# eurorack-passive-diodefuzz-5switches.net
KiCad netlist of a schematic drawn in EAGLE
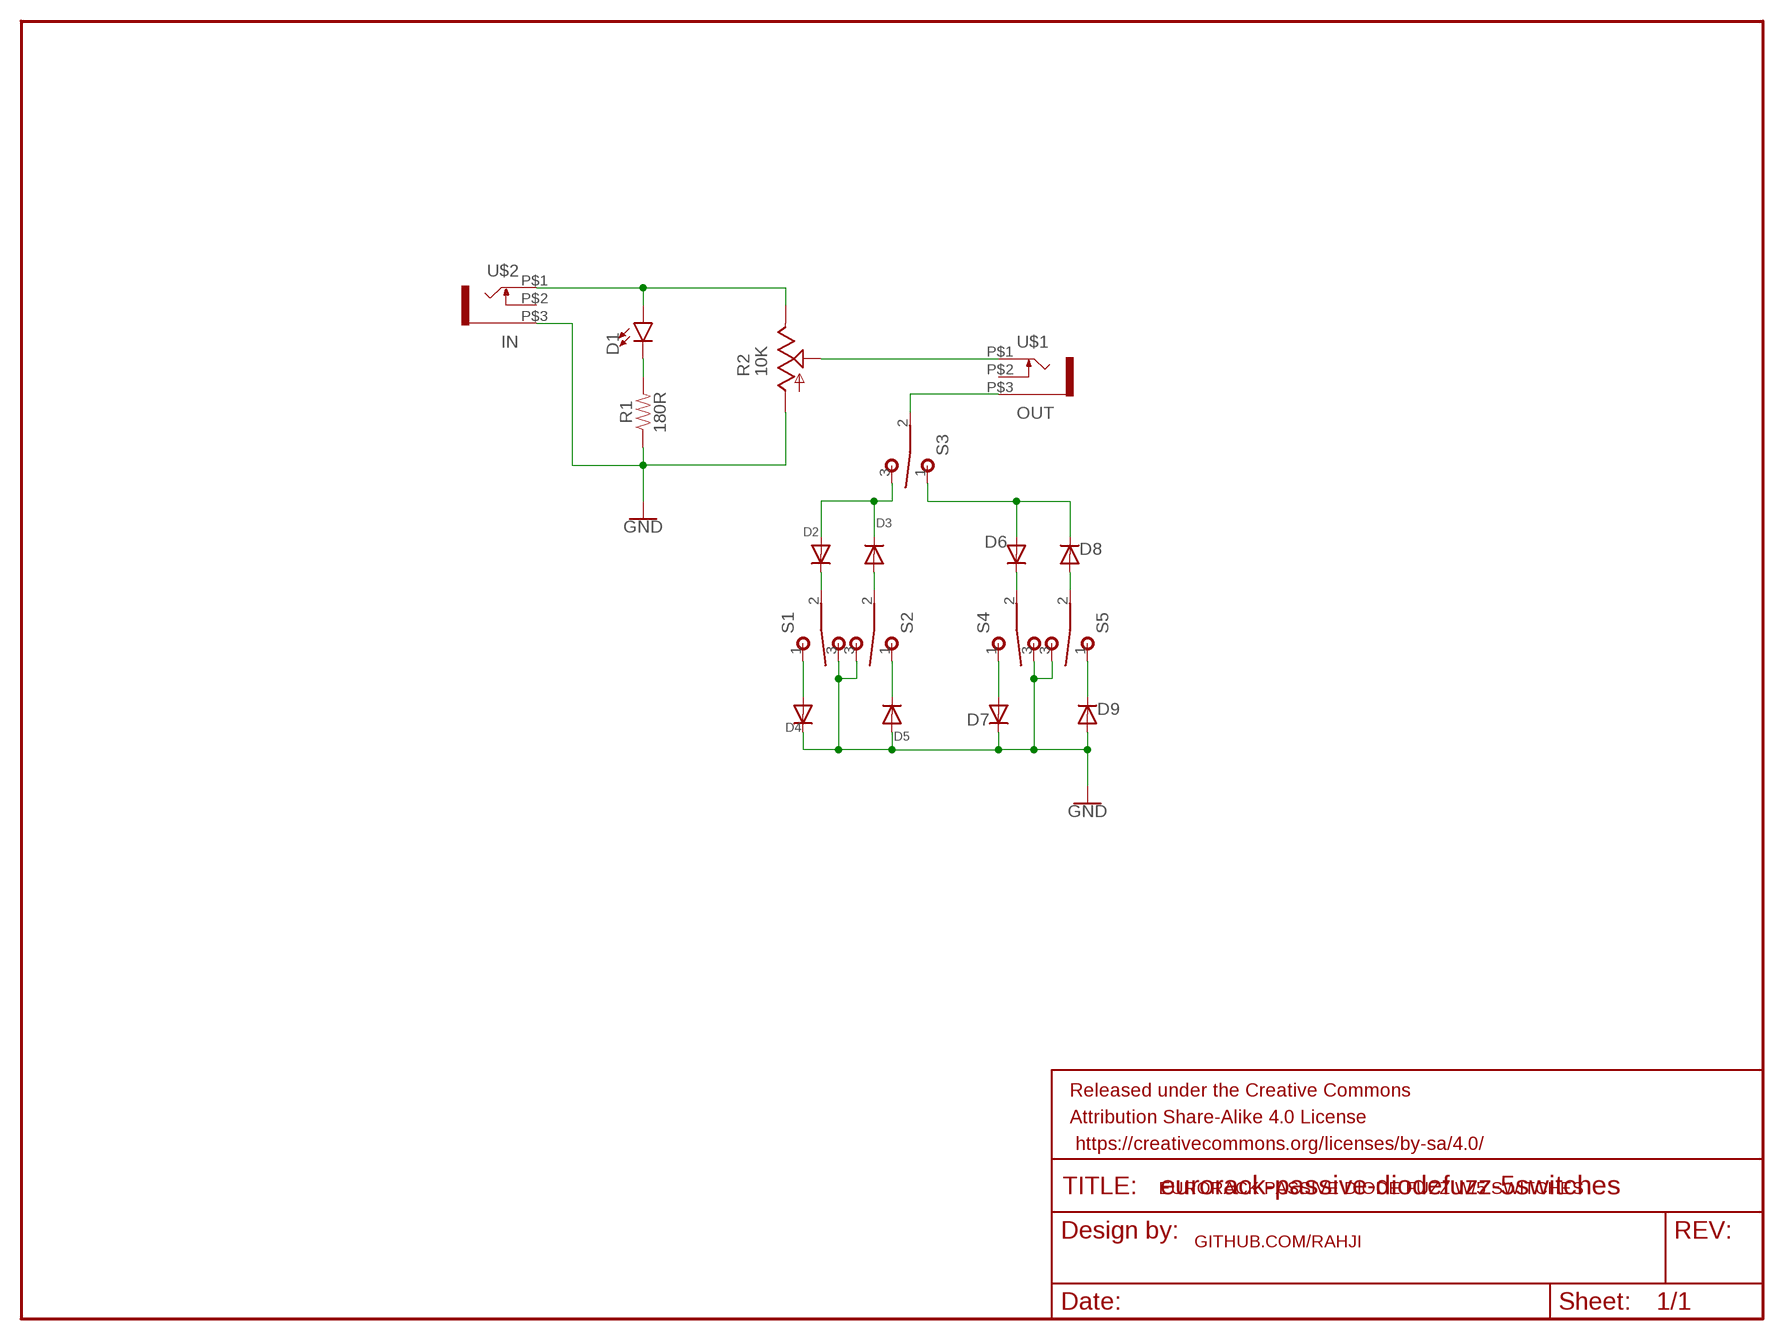
[diagram p0: schematic, sheet 1]

(export (version "E")
  (design (tool "Eeschema 10.0.6"))
  (components
    (comp (ref "D1")
      (value "LED5MM")
      (footprint "eagle-import:LED_5MM")
      (libsource (lib "eagle-import") (part "LED5MM"))
    )
    (comp (ref "D2")
      (value "VERTICAL_DIODE")
      (footprint "eagle-import:C1702-05")
      (libsource (lib "eagle-import") (part "VERTICAL_DIODE"))
    )
    (comp (ref "D3")
      (value "VERTICAL_DIODE")
      (footprint "eagle-import:C1702-05")
      (libsource (lib "eagle-import") (part "VERTICAL_DIODE"))
    )
    (comp (ref "D4")
      (value "VERTICAL_DIODE")
      (footprint "eagle-import:C1702-05")
      (libsource (lib "eagle-import") (part "VERTICAL_DIODE"))
    )
    (comp (ref "D5")
      (value "VERTICAL_DIODE")
      (footprint "eagle-import:C1702-05")
      (libsource (lib "eagle-import") (part "VERTICAL_DIODE"))
    )
    (comp (ref "D6")
      (value "VERTICAL_DIODE")
      (footprint "eagle-import:C1702-05")
      (libsource (lib "eagle-import") (part "VERTICAL_DIODE"))
    )
    (comp (ref "D7")
      (value "VERTICAL_DIODE")
      (footprint "eagle-import:C1702-05")
      (libsource (lib "eagle-import") (part "VERTICAL_DIODE"))
    )
    (comp (ref "D8")
      (value "VERTICAL_DIODE")
      (footprint "eagle-import:C1702-05")
      (libsource (lib "eagle-import") (part "VERTICAL_DIODE"))
    )
    (comp (ref "D9")
      (value "VERTICAL_DIODE")
      (footprint "eagle-import:C1702-05")
      (libsource (lib "eagle-import") (part "VERTICAL_DIODE"))
    )
    (comp (ref "FRAME1")
      (value "FRAME-LETTERNO_PACKAGE")
      (footprint "eagle-import:DUMMY")
      (fields (field (name "DESIGNER") "Nobody"))
      (libsource (lib "eagle-import") (part "FRAME-LETTERNO_PACKAGE"))
    )
    (comp (ref "R1")
      (value "180R")
      (footprint "eagle-import:AXIAL-0.3")
      (libsource (lib "eagle-import") (part "330OHM-HORIZ-1/10W-5%"))
    )
    (comp (ref "R2")
      (value "10K")
      (footprint "eagle-import:EVUF")
      (libsource (lib "eagle-import") (part "ALPHA-9MMAF3"))
    )
    (comp (ref "S1")
      (value "SPDT")
      (footprint "eagle-import:M9040P")
      (libsource (lib "eagle-import") (part "SPDT"))
    )
    (comp (ref "S2")
      (value "SPDT")
      (footprint "eagle-import:M9040P")
      (libsource (lib "eagle-import") (part "SPDT"))
    )
    (comp (ref "S3")
      (value "SPDT")
      (footprint "eagle-import:M9040P")
      (libsource (lib "eagle-import") (part "SPDT"))
    )
    (comp (ref "S4")
      (value "SPDT")
      (footprint "eagle-import:M9040P")
      (libsource (lib "eagle-import") (part "SPDT"))
    )
    (comp (ref "S5")
      (value "SPDT")
      (footprint "eagle-import:M9040P")
      (libsource (lib "eagle-import") (part "SPDT"))
    )
    (comp (ref "U$1")
      (value "OUT")
      (footprint "eagle-import:WQP-PJ301M-12_JACK")
      (libsource (lib "eagle-import") (part "WQP-PJ301M-12_JACK"))
    )
    (comp (ref "U$2")
      (value "IN")
      (footprint "eagle-import:WQP-PJ301M-12_JACK")
      (libsource (lib "eagle-import") (part "WQP-PJ301M-12_JACK"))
    )
  )
  (nets
    (net (code "1") (name "GND") (class "Default")
      (node (ref "D4") (pin "C") (pinfunction "C_C") (pintype "passive"))
      (node (ref "D5") (pin "A") (pinfunction "A_A") (pintype "passive"))
      (node (ref "D7") (pin "C") (pinfunction "C_C") (pintype "passive"))
      (node (ref "D9") (pin "A") (pinfunction "A_A") (pintype "passive"))
      (node (ref "R1") (pin "P$1") (pinfunction "1_P$1") (pintype "passive"))
      (node (ref "R2") (pin "1") (pinfunction "A_1") (pintype "passive"))
      (node (ref "S1") (pin "3") (pinfunction "S_3") (pintype "passive"))
      (node (ref "S2") (pin "3") (pinfunction "S_3") (pintype "passive"))
      (node (ref "S4") (pin "3") (pinfunction "S_3") (pintype "passive"))
      (node (ref "S5") (pin "3") (pinfunction "S_3") (pintype "passive"))
      (node (ref "U$2") (pin "P$3") (pinfunction "1_P$3") (pintype "passive"))
    )
    (net (code "2") (name "Net-(D1-C)") (class "Default")
      (node (ref "D1") (pin "K") (pinfunction "C_K") (pintype "passive"))
      (node (ref "R1") (pin "P$2") (pinfunction "2_P$2") (pintype "passive"))
    )
    (net (code "3") (name "Net-(R2-E)") (class "Default")
      (node (ref "D1") (pin "A") (pinfunction "A_A") (pintype "passive"))
      (node (ref "R2") (pin "3") (pinfunction "E_3") (pintype "passive"))
      (node (ref "U$2") (pin "P$1") (pinfunction "2_P$1") (pintype "passive"))
    )
    (net (code "4") (name "Net-(R2-S)") (class "Default")
      (node (ref "R2") (pin "2") (pinfunction "S_2") (pintype "passive"))
      (node (ref "U$1") (pin "P$1") (pinfunction "2_P$1") (pintype "passive"))
    )
    (net (code "5") (name "Net-(S1-O)") (class "Default")
      (node (ref "D4") (pin "A") (pinfunction "A_A") (pintype "passive"))
      (node (ref "S1") (pin "1") (pinfunction "O_1") (pintype "passive"))
    )
    (net (code "6") (name "Net-(S1-P)") (class "Default")
      (node (ref "D2") (pin "C") (pinfunction "C_C") (pintype "passive"))
      (node (ref "S1") (pin "2") (pinfunction "P_2") (pintype "passive"))
    )
    (net (code "7") (name "Net-(S2-O)") (class "Default")
      (node (ref "D5") (pin "C") (pinfunction "C_C") (pintype "passive"))
      (node (ref "S2") (pin "1") (pinfunction "O_1") (pintype "passive"))
    )
    (net (code "8") (name "Net-(S2-P)") (class "Default")
      (node (ref "D3") (pin "A") (pinfunction "A_A") (pintype "passive"))
      (node (ref "S2") (pin "2") (pinfunction "P_2") (pintype "passive"))
    )
    (net (code "9") (name "Net-(S3-O)") (class "Default")
      (node (ref "D6") (pin "A") (pinfunction "A_A") (pintype "passive"))
      (node (ref "D8") (pin "C") (pinfunction "C_C") (pintype "passive"))
      (node (ref "S3") (pin "1") (pinfunction "O_1") (pintype "passive"))
    )
    (net (code "10") (name "Net-(S3-P)") (class "Default")
      (node (ref "S3") (pin "2") (pinfunction "P_2") (pintype "passive"))
      (node (ref "U$1") (pin "P$3") (pinfunction "1_P$3") (pintype "passive"))
    )
    (net (code "11") (name "Net-(S3-S)") (class "Default")
      (node (ref "D2") (pin "A") (pinfunction "A_A") (pintype "passive"))
      (node (ref "D3") (pin "C") (pinfunction "C_C") (pintype "passive"))
      (node (ref "S3") (pin "3") (pinfunction "S_3") (pintype "passive"))
    )
    (net (code "12") (name "Net-(S4-O)") (class "Default")
      (node (ref "D7") (pin "A") (pinfunction "A_A") (pintype "passive"))
      (node (ref "S4") (pin "1") (pinfunction "O_1") (pintype "passive"))
    )
    (net (code "13") (name "Net-(S4-P)") (class "Default")
      (node (ref "D6") (pin "C") (pinfunction "C_C") (pintype "passive"))
      (node (ref "S4") (pin "2") (pinfunction "P_2") (pintype "passive"))
    )
    (net (code "14") (name "Net-(S5-O)") (class "Default")
      (node (ref "D9") (pin "C") (pinfunction "C_C") (pintype "passive"))
      (node (ref "S5") (pin "1") (pinfunction "O_1") (pintype "passive"))
    )
    (net (code "15") (name "Net-(S5-P)") (class "Default")
      (node (ref "D8") (pin "A") (pinfunction "A_A") (pintype "passive"))
      (node (ref "S5") (pin "2") (pinfunction "P_2") (pintype "passive"))
    )
    (net (code "16") (name "unconnected-(U$1-3-PadP$2)") (class "Default")
      (node (ref "U$1") (pin "P$2") (pinfunction "3_P$2") (pintype "passive"))
    )
    (net (code "17") (name "unconnected-(U$2-3-PadP$2)") (class "Default")
      (node (ref "U$2") (pin "P$2") (pinfunction "3_P$2") (pintype "passive"))
    )
  )
)
